# main_schematic.net
KiCad netlist of a schematic drawn in EAGLE
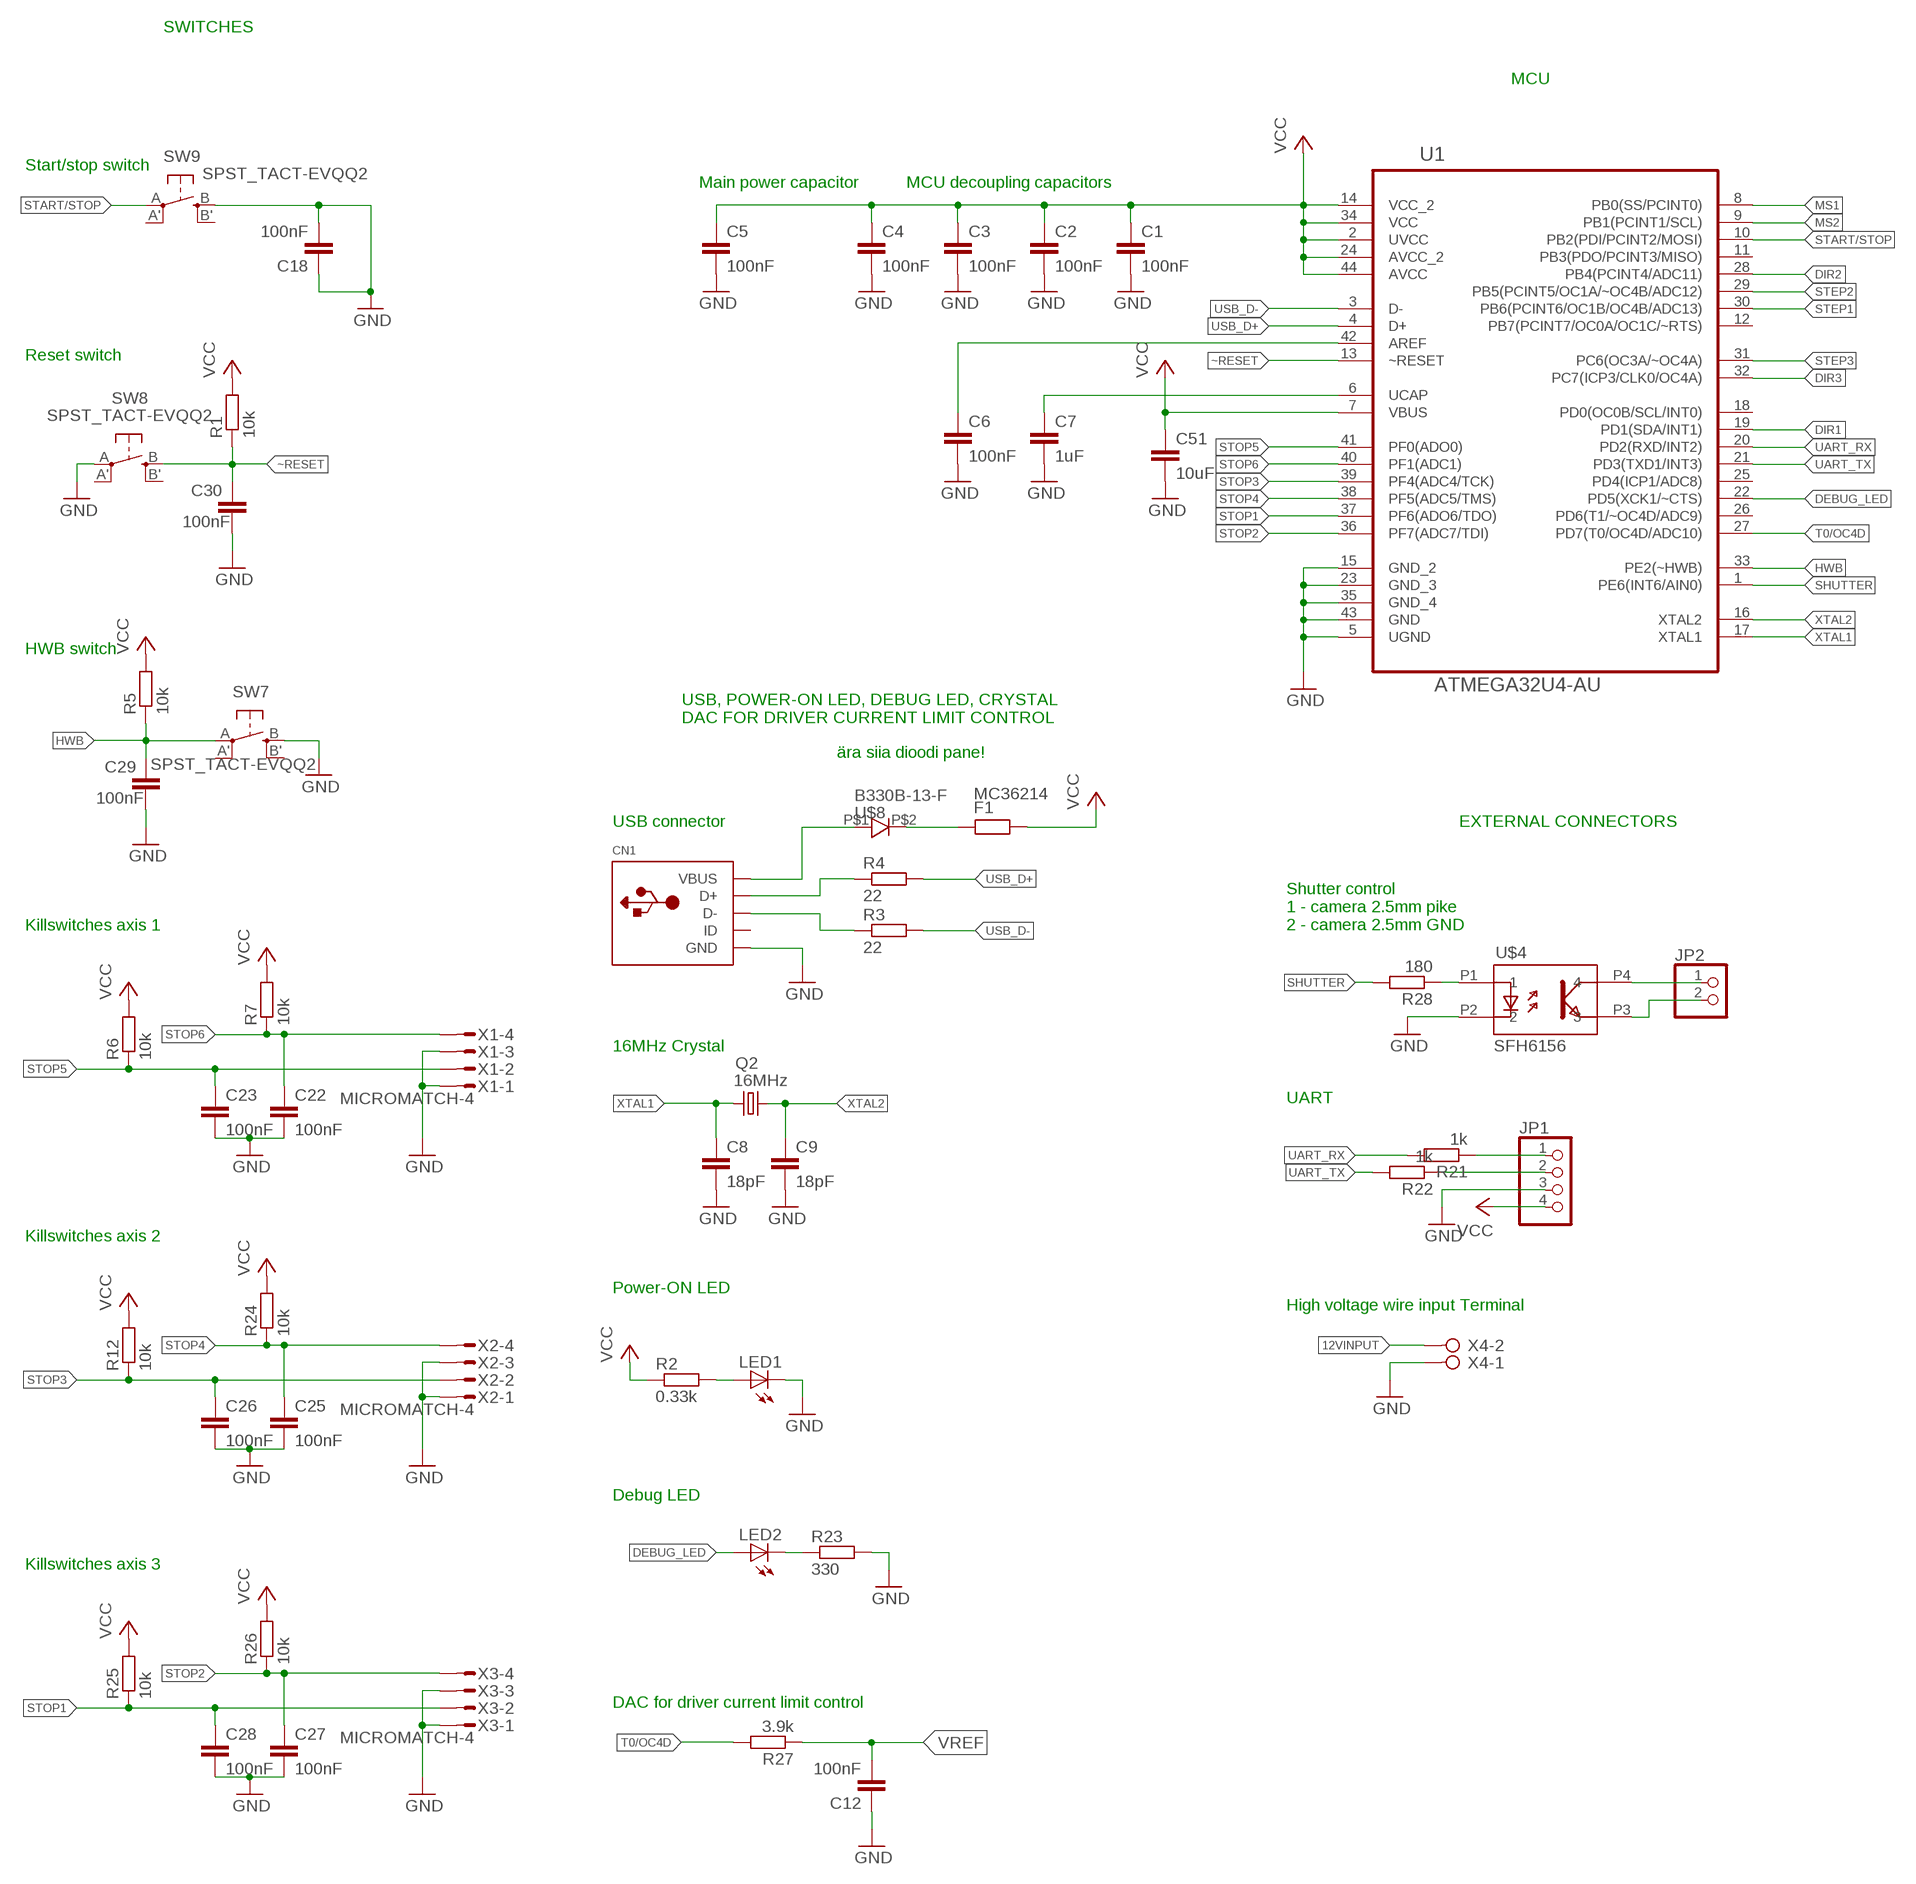
[diagram p0: schematic, sheet 1, part 1 of 2]
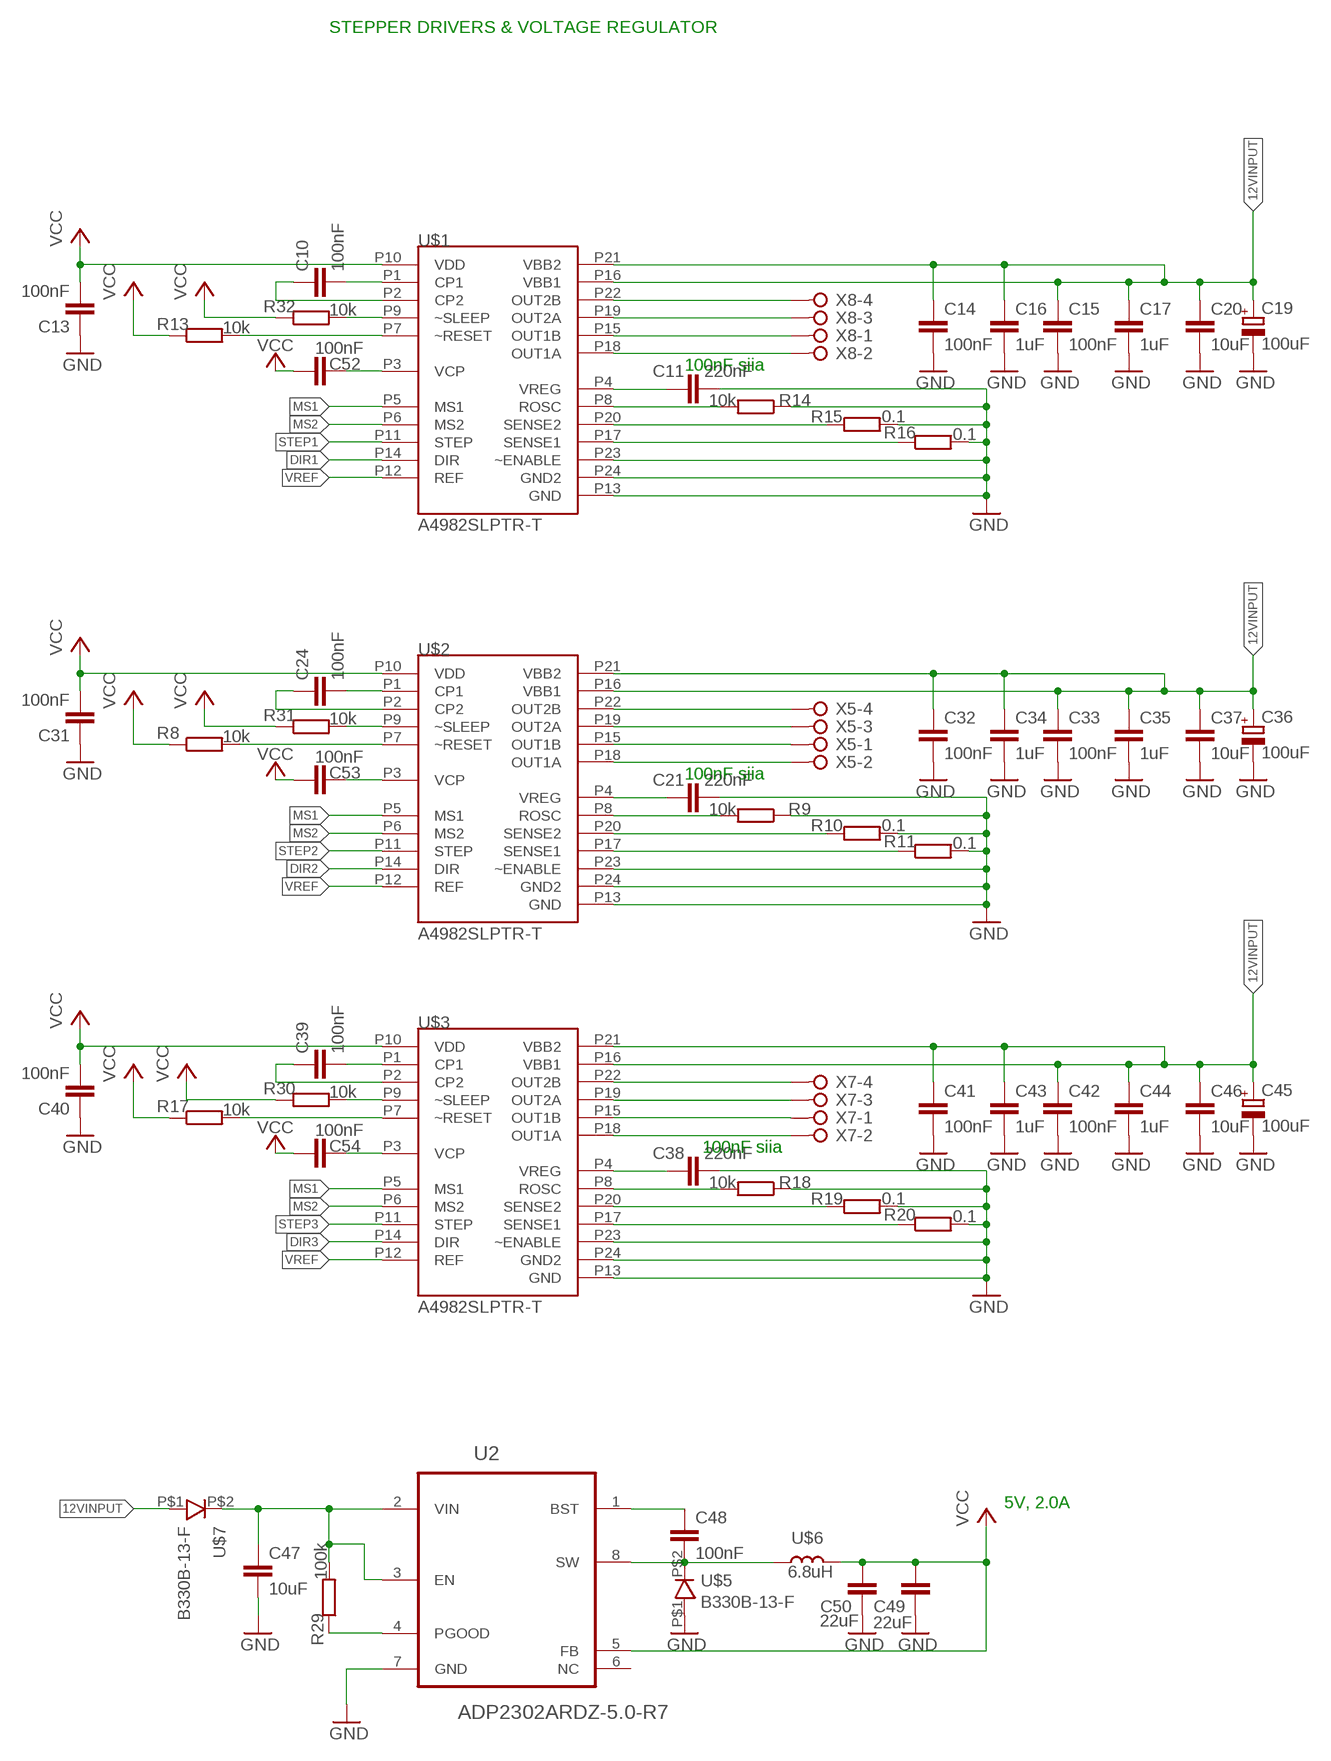
[diagram p1: schematic, sheet 1, part 2 of 2]

(export (version "E")
  (design (tool "Eeschema 10.0.6"))
  (components
    (comp (ref "C1")
      (value "100nF")
      (footprint "eagle-import:C0603K")
      (libsource (lib "eagle-import") (part "C-EUC0603K"))
    )
    (comp (ref "C2")
      (value "100nF")
      (footprint "eagle-import:C0603K")
      (libsource (lib "eagle-import") (part "C-EUC0603K"))
    )
    (comp (ref "C3")
      (value "100nF")
      (footprint "eagle-import:C0603K")
      (libsource (lib "eagle-import") (part "C-EUC0603K"))
    )
    (comp (ref "C4")
      (value "100nF")
      (footprint "eagle-import:C0603K")
      (libsource (lib "eagle-import") (part "C-EUC0603K"))
    )
    (comp (ref "C5")
      (value "100nF")
      (footprint "eagle-import:C0603K")
      (libsource (lib "eagle-import") (part "C-EUC0603K"))
    )
    (comp (ref "C6")
      (value "100nF")
      (footprint "eagle-import:C0603K")
      (libsource (lib "eagle-import") (part "C-EUC0603K"))
    )
    (comp (ref "C7")
      (value "1uF")
      (footprint "eagle-import:C0603K")
      (libsource (lib "eagle-import") (part "C-EUC0603K"))
    )
    (comp (ref "C8")
      (value "18pF")
      (footprint "eagle-import:C0603K")
      (libsource (lib "eagle-import") (part "C-EUC0603K"))
    )
    (comp (ref "C9")
      (value "18pF")
      (footprint "eagle-import:C0603K")
      (libsource (lib "eagle-import") (part "C-EUC0603K"))
    )
    (comp (ref "C10")
      (value "100nF")
      (footprint "eagle-import:C0603K")
      (libsource (lib "eagle-import") (part "C-EUC0603K"))
    )
    (comp (ref "C11")
      (value "220nF")
      (footprint "eagle-import:C0603K")
      (libsource (lib "eagle-import") (part "C-EUC0603K"))
    )
    (comp (ref "C12")
      (value "100nF")
      (footprint "eagle-import:C0603K")
      (libsource (lib "eagle-import") (part "C-EUC0603K"))
    )
    (comp (ref "C13")
      (value "100nF")
      (footprint "eagle-import:C0603K")
      (libsource (lib "eagle-import") (part "C-EUC0603K"))
    )
    (comp (ref "C14")
      (value "100nF")
      (footprint "eagle-import:C0603K")
      (libsource (lib "eagle-import") (part "C-EUC0603K"))
    )
    (comp (ref "C15")
      (value "100nF")
      (footprint "eagle-import:C0603K")
      (libsource (lib "eagle-import") (part "C-EUC0603K"))
    )
    (comp (ref "C16")
      (value "1uF")
      (footprint "eagle-import:C0603K")
      (libsource (lib "eagle-import") (part "C-EUC0603K"))
    )
    (comp (ref "C17")
      (value "1uF")
      (footprint "eagle-import:C0603K")
      (libsource (lib "eagle-import") (part "C-EUC0603K"))
    )
    (comp (ref "C18")
      (value "100nF")
      (footprint "eagle-import:C0603K")
      (libsource (lib "eagle-import") (part "C-EUC0603K"))
    )
    (comp (ref "C19")
      (value "100uF")
      (footprint "eagle-import:E_7260-38R")
      (libsource (lib "eagle-import") (part "CPOL-EUE/7260-38R"))
    )
    (comp (ref "C20")
      (value "10uF")
      (footprint "eagle-import:C1206K")
      (libsource (lib "eagle-import") (part "C-EUC1206K"))
    )
    (comp (ref "C21")
      (value "220nF")
      (footprint "eagle-import:C0603K")
      (libsource (lib "eagle-import") (part "C-EUC0603K"))
    )
    (comp (ref "C22")
      (value "100nF")
      (footprint "eagle-import:C0603K")
      (libsource (lib "eagle-import") (part "C-EUC0603K"))
    )
    (comp (ref "C23")
      (value "100nF")
      (footprint "eagle-import:C0603K")
      (libsource (lib "eagle-import") (part "C-EUC0603K"))
    )
    (comp (ref "C24")
      (value "100nF")
      (footprint "eagle-import:C0603K")
      (libsource (lib "eagle-import") (part "C-EUC0603K"))
    )
    (comp (ref "C25")
      (value "100nF")
      (footprint "eagle-import:C0603K")
      (libsource (lib "eagle-import") (part "C-EUC0603K"))
    )
    (comp (ref "C26")
      (value "100nF")
      (footprint "eagle-import:C0603K")
      (libsource (lib "eagle-import") (part "C-EUC0603K"))
    )
    (comp (ref "C27")
      (value "100nF")
      (footprint "eagle-import:C0603K")
      (libsource (lib "eagle-import") (part "C-EUC0603K"))
    )
    (comp (ref "C28")
      (value "100nF")
      (footprint "eagle-import:C0603K")
      (libsource (lib "eagle-import") (part "C-EUC0603K"))
    )
    (comp (ref "C29")
      (value "100nF")
      (footprint "eagle-import:C0603K")
      (libsource (lib "eagle-import") (part "C-EUC0603K"))
    )
    (comp (ref "C30")
      (value "100nF")
      (footprint "eagle-import:C0603K")
      (libsource (lib "eagle-import") (part "C-EUC0603K"))
    )
    (comp (ref "C31")
      (value "100nF")
      (footprint "eagle-import:C0603K")
      (libsource (lib "eagle-import") (part "C-EUC0603K"))
    )
    (comp (ref "C32")
      (value "100nF")
      (footprint "eagle-import:C0603K")
      (libsource (lib "eagle-import") (part "C-EUC0603K"))
    )
    (comp (ref "C33")
      (value "100nF")
      (footprint "eagle-import:C0603K")
      (libsource (lib "eagle-import") (part "C-EUC0603K"))
    )
    (comp (ref "C34")
      (value "1uF")
      (footprint "eagle-import:C0603K")
      (libsource (lib "eagle-import") (part "C-EUC0603K"))
    )
    (comp (ref "C35")
      (value "1uF")
      (footprint "eagle-import:C0603K")
      (libsource (lib "eagle-import") (part "C-EUC0603K"))
    )
    (comp (ref "C36")
      (value "100uF")
      (footprint "eagle-import:E_7260-38R")
      (libsource (lib "eagle-import") (part "CPOL-EUE/7260-38R"))
    )
    (comp (ref "C37")
      (value "10uF")
      (footprint "eagle-import:C1206K")
      (libsource (lib "eagle-import") (part "C-EUC1206K"))
    )
    (comp (ref "C38")
      (value "220nF")
      (footprint "eagle-import:C0603K")
      (libsource (lib "eagle-import") (part "C-EUC0603K"))
    )
    (comp (ref "C39")
      (value "100nF")
      (footprint "eagle-import:C0603K")
      (libsource (lib "eagle-import") (part "C-EUC0603K"))
    )
    (comp (ref "C40")
      (value "100nF")
      (footprint "eagle-import:C0603K")
      (libsource (lib "eagle-import") (part "C-EUC0603K"))
    )
    (comp (ref "C41")
      (value "100nF")
      (footprint "eagle-import:C0603K")
      (libsource (lib "eagle-import") (part "C-EUC0603K"))
    )
    (comp (ref "C42")
      (value "100nF")
      (footprint "eagle-import:C0603K")
      (libsource (lib "eagle-import") (part "C-EUC0603K"))
    )
    (comp (ref "C43")
      (value "1uF")
      (footprint "eagle-import:C0603K")
      (libsource (lib "eagle-import") (part "C-EUC0603K"))
    )
    (comp (ref "C44")
      (value "1uF")
      (footprint "eagle-import:C0603K")
      (libsource (lib "eagle-import") (part "C-EUC0603K"))
    )
    (comp (ref "C45")
      (value "100uF")
      (footprint "eagle-import:E_7260-38R")
      (libsource (lib "eagle-import") (part "CPOL-EUE/7260-38R"))
    )
    (comp (ref "C46")
      (value "10uF")
      (footprint "eagle-import:C1206K")
      (libsource (lib "eagle-import") (part "C-EUC1206K"))
    )
    (comp (ref "C47")
      (value "10uF")
      (footprint "eagle-import:C1206K")
      (libsource (lib "eagle-import") (part "C-EUC1206K"))
    )
    (comp (ref "C48")
      (value "100nF")
      (footprint "eagle-import:C1206K")
      (libsource (lib "eagle-import") (part "C-EUC1206K"))
    )
    (comp (ref "C49")
      (value "22uF")
      (footprint "eagle-import:C1206K")
      (libsource (lib "eagle-import") (part "C-EUC1206K"))
    )
    (comp (ref "C50")
      (value "22uF")
      (footprint "eagle-import:C1206K")
      (libsource (lib "eagle-import") (part "C-EUC1206K"))
    )
    (comp (ref "C51")
      (value "10uF")
      (footprint "eagle-import:C0805")
      (libsource (lib "eagle-import") (part "C-EUC0805"))
    )
    (comp (ref "C52")
      (value "100nF")
      (footprint "eagle-import:C0603K")
      (libsource (lib "eagle-import") (part "C-EUC0603K"))
    )
    (comp (ref "C53")
      (value "100nF")
      (footprint "eagle-import:C0603K")
      (libsource (lib "eagle-import") (part "C-EUC0603K"))
    )
    (comp (ref "C54")
      (value "100nF")
      (footprint "eagle-import:C0603K")
      (libsource (lib "eagle-import") (part "C-EUC0603K"))
    )
    (comp (ref "CN1")
      (value "USBMINIB")
      (footprint "eagle-import:USB-MINIB")
      (libsource (lib "eagle-import") (part "USBMINIB"))
    )
    (comp (ref "F1")
      (value "MC36214")
      (footprint "eagle-import:MC36214")
      (libsource (lib "eagle-import") (part "MC36214"))
    )
    (comp (ref "JP1")
      (value "PINHD-1X4")
      (footprint "eagle-import:1X04")
      (libsource (lib "eagle-import") (part "PINHD-1X4"))
    )
    (comp (ref "JP2")
      (value "PINHD-1X2")
      (footprint "eagle-import:1X02")
      (libsource (lib "eagle-import") (part "PINHD-1X2"))
    )
    (comp (ref "LED1")
      (value "LEDCHIP-LED0603")
      (footprint "eagle-import:CHIP-LED0603")
      (libsource (lib "eagle-import") (part "LEDCHIP-LED0603"))
    )
    (comp (ref "LED2")
      (value "LEDCHIP-LED0603")
      (footprint "eagle-import:CHIP-LED0603")
      (libsource (lib "eagle-import") (part "LEDCHIP-LED0603"))
    )
    (comp (ref "Q2")
      (value "16MHz")
      (footprint "eagle-import:SM49")
      (libsource (lib "eagle-import") (part "CRYSTALSM49"))
    )
    (comp (ref "R1")
      (value "10k")
      (footprint "eagle-import:R0603")
      (libsource (lib "eagle-import") (part "R-EU_R0603"))
    )
    (comp (ref "R2")
      (value "0.33k")
      (footprint "eagle-import:R0603")
      (libsource (lib "eagle-import") (part "R-EU_R0603"))
    )
    (comp (ref "R3")
      (value "22")
      (footprint "eagle-import:R0603")
      (libsource (lib "eagle-import") (part "R-EU_R0603"))
    )
    (comp (ref "R4")
      (value "22")
      (footprint "eagle-import:R0603")
      (libsource (lib "eagle-import") (part "R-EU_R0603"))
    )
    (comp (ref "R5")
      (value "10k")
      (footprint "eagle-import:R0603")
      (libsource (lib "eagle-import") (part "R-EU_R0603"))
    )
    (comp (ref "R6")
      (value "10k")
      (footprint "eagle-import:R0603")
      (libsource (lib "eagle-import") (part "R-EU_R0603"))
    )
    (comp (ref "R7")
      (value "10k")
      (footprint "eagle-import:R0603")
      (libsource (lib "eagle-import") (part "R-EU_R0603"))
    )
    (comp (ref "R8")
      (value "10k")
      (footprint "eagle-import:R0603")
      (libsource (lib "eagle-import") (part "R-EU_R0603"))
    )
    (comp (ref "R9")
      (value "10k")
      (footprint "eagle-import:R0603")
      (libsource (lib "eagle-import") (part "R-EU_R0603"))
    )
    (comp (ref "R10")
      (value "0.1")
      (footprint "eagle-import:R0805")
      (libsource (lib "eagle-import") (part "R-EU_R0805"))
    )
    (comp (ref "R11")
      (value "0.1")
      (footprint "eagle-import:R0805")
      (libsource (lib "eagle-import") (part "R-EU_R0805"))
    )
    (comp (ref "R12")
      (value "10k")
      (footprint "eagle-import:R0603")
      (libsource (lib "eagle-import") (part "R-EU_R0603"))
    )
    (comp (ref "R13")
      (value "10k")
      (footprint "eagle-import:R0603")
      (libsource (lib "eagle-import") (part "R-EU_R0603"))
    )
    (comp (ref "R14")
      (value "10k")
      (footprint "eagle-import:R0603")
      (libsource (lib "eagle-import") (part "R-EU_R0603"))
    )
    (comp (ref "R15")
      (value "0.1")
      (footprint "eagle-import:R0805")
      (libsource (lib "eagle-import") (part "R-EU_R0805"))
    )
    (comp (ref "R16")
      (value "0.1")
      (footprint "eagle-import:R0805")
      (libsource (lib "eagle-import") (part "R-EU_R0805"))
    )
    (comp (ref "R17")
      (value "10k")
      (footprint "eagle-import:R0603")
      (libsource (lib "eagle-import") (part "R-EU_R0603"))
    )
    (comp (ref "R18")
      (value "10k")
      (footprint "eagle-import:R0603")
      (libsource (lib "eagle-import") (part "R-EU_R0603"))
    )
    (comp (ref "R19")
      (value "0.1")
      (footprint "eagle-import:R0805")
      (libsource (lib "eagle-import") (part "R-EU_R0805"))
    )
    (comp (ref "R20")
      (value "0.1")
      (footprint "eagle-import:R0805")
      (libsource (lib "eagle-import") (part "R-EU_R0805"))
    )
    (comp (ref "R21")
      (value "1k")
      (footprint "eagle-import:R0603")
      (libsource (lib "eagle-import") (part "R-EU_R0603"))
    )
    (comp (ref "R22")
      (value "1k")
      (footprint "eagle-import:R0603")
      (libsource (lib "eagle-import") (part "R-EU_R0603"))
    )
    (comp (ref "R23")
      (value "330")
      (footprint "eagle-import:R0603")
      (libsource (lib "eagle-import") (part "R-EU_R0603"))
    )
    (comp (ref "R24")
      (value "10k")
      (footprint "eagle-import:R0603")
      (libsource (lib "eagle-import") (part "R-EU_R0603"))
    )
    (comp (ref "R25")
      (value "10k")
      (footprint "eagle-import:R0603")
      (libsource (lib "eagle-import") (part "R-EU_R0603"))
    )
    (comp (ref "R26")
      (value "10k")
      (footprint "eagle-import:R0603")
      (libsource (lib "eagle-import") (part "R-EU_R0603"))
    )
    (comp (ref "R27")
      (value "3.9k")
      (footprint "eagle-import:R0603")
      (libsource (lib "eagle-import") (part "R-EU_R0603"))
    )
    (comp (ref "R28")
      (value "180")
      (footprint "eagle-import:R0603")
      (libsource (lib "eagle-import") (part "R-EU_R0603"))
    )
    (comp (ref "R29")
      (value "100k")
      (footprint "eagle-import:R0603")
      (libsource (lib "eagle-import") (part "R-EU_R0603"))
    )
    (comp (ref "R30")
      (value "10k")
      (footprint "eagle-import:R0603")
      (libsource (lib "eagle-import") (part "R-EU_R0603"))
    )
    (comp (ref "R31")
      (value "10k")
      (footprint "eagle-import:R0603")
      (libsource (lib "eagle-import") (part "R-EU_R0603"))
    )
    (comp (ref "R32")
      (value "10k")
      (footprint "eagle-import:R0603")
      (libsource (lib "eagle-import") (part "R-EU_R0603"))
    )
    (comp (ref "SW7")
      (value "SPST_TACT-EVQQ2")
      (footprint "eagle-import:EVQ-Q2")
      (libsource (lib "eagle-import") (part "SPST_TACT-EVQQ2"))
    )
    (comp (ref "SW8")
      (value "SPST_TACT-EVQQ2")
      (footprint "eagle-import:EVQ-Q2")
      (libsource (lib "eagle-import") (part "SPST_TACT-EVQQ2"))
    )
    (comp (ref "SW9")
      (value "SPST_TACT-EVQQ2")
      (footprint "eagle-import:EVQ-Q2")
      (libsource (lib "eagle-import") (part "SPST_TACT-EVQQ2"))
    )
    (comp (ref "U$1")
      (value "A4982SLPTR-T")
      (footprint "eagle-import:TSSOP_24")
      (libsource (lib "eagle-import") (part "A4982SLPTR-T"))
    )
    (comp (ref "U$2")
      (value "A4982SLPTR-T")
      (footprint "eagle-import:TSSOP_24")
      (libsource (lib "eagle-import") (part "A4982SLPTR-T"))
    )
    (comp (ref "U$3")
      (value "A4982SLPTR-T")
      (footprint "eagle-import:TSSOP_24")
      (libsource (lib "eagle-import") (part "A4982SLPTR-T"))
    )
    (comp (ref "U$4")
      (value "SFH6156")
      (footprint "eagle-import:SFH6165")
      (libsource (lib "eagle-import") (part "SFH6156"))
    )
    (comp (ref "U$5")
      (value "B330B-13-F")
      (footprint "eagle-import:B330B-13-F")
      (libsource (lib "eagle-import") (part "SCHOTTK_YB330B-13-F"))
    )
    (comp (ref "U$6")
      (value "6.8uH")
      (footprint "eagle-import:VLF10040")
      (libsource (lib "eagle-import") (part "VLF10040"))
    )
    (comp (ref "U$7")
      (value "B330B-13-F")
      (footprint "eagle-import:B330B-13-F")
      (libsource (lib "eagle-import") (part "SCHOTTK_YB330B-13-F"))
    )
    (comp (ref "U$8")
      (value "B330B-13-F")
      (footprint "eagle-import:B330B-13-F")
      (libsource (lib "eagle-import") (part "SCHOTTK_YB330B-13-F"))
    )
    (comp (ref "U1")
      (value "ATMEGA32U4-AU")
      (footprint "eagle-import:QFP80P1200X1200X120-44N")
      (libsource (lib "eagle-import") (part "ATMEGA32U4-AU"))
    )
    (comp (ref "U2")
      (value "ADP2302ARDZ-5.0-R7")
      (footprint "eagle-import:SOIC127P600X175-9N")
      (libsource (lib "eagle-import") (part "ADP2302ARDZ-5.0-R7"))
    )
    (comp (ref "X1")
      (value "MICROMATCH-4")
      (footprint "eagle-import:MICROMATCH-4")
      (fields (field (name "MPN") "7-215464-4"))
      (libsource (lib "eagle-import") (part "MICROMATCH-4"))
    )
    (comp (ref "X2")
      (value "MICROMATCH-4")
      (footprint "eagle-import:MICROMATCH-4")
      (fields (field (name "MPN") "7-215464-4"))
      (libsource (lib "eagle-import") (part "MICROMATCH-4"))
    )
    (comp (ref "X3")
      (value "MICROMATCH-4")
      (footprint "eagle-import:MICROMATCH-4")
      (fields (field (name "MPN") "7-215464-4"))
      (libsource (lib "eagle-import") (part "MICROMATCH-4"))
    )
    (comp (ref "X4")
      (value "W237-02P")
      (footprint "eagle-import:W237-132")
      (libsource (lib "eagle-import") (part "W237-02P"))
    )
    (comp (ref "X5")
      (value "W237-04P")
      (footprint "eagle-import:W237-4P")
      (libsource (lib "eagle-import") (part "W237-04P"))
    )
    (comp (ref "X7")
      (value "W237-04P")
      (footprint "eagle-import:W237-4P")
      (libsource (lib "eagle-import") (part "W237-04P"))
    )
    (comp (ref "X8")
      (value "W237-04P")
      (footprint "eagle-import:W237-4P")
      (libsource (lib "eagle-import") (part "W237-04P"))
    )
  )
  (nets
    (net (code "1") (name "/~{RESET}") (class "Default")
      (node (ref "C30") (pin "1") (pinfunction "1_1") (pintype "passive"))
      (node (ref "R1") (pin "1") (pinfunction "1_1") (pintype "passive"))
      (node (ref "SW8") (pin "B") (pinfunction "S_B") (pintype "passive"))
      (node (ref "U1") (pin "13") (pinfunction "~{RESET}_13") (pintype "input"))
    )
    (net (code "2") (name "12VINPUT") (class "Default")
      (node (ref "C14") (pin "1") (pinfunction "1_1") (pintype "passive"))
      (node (ref "C15") (pin "1") (pinfunction "1_1") (pintype "passive"))
      (node (ref "C16") (pin "1") (pinfunction "1_1") (pintype "passive"))
      (node (ref "C17") (pin "1") (pinfunction "1_1") (pintype "passive"))
      (node (ref "C19") (pin "+") (pinfunction "+_+") (pintype "passive"))
      (node (ref "C20") (pin "1") (pinfunction "1_1") (pintype "passive"))
      (node (ref "C32") (pin "1") (pinfunction "1_1") (pintype "passive"))
      (node (ref "C33") (pin "1") (pinfunction "1_1") (pintype "passive"))
      (node (ref "C34") (pin "1") (pinfunction "1_1") (pintype "passive"))
      (node (ref "C35") (pin "1") (pinfunction "1_1") (pintype "passive"))
      (node (ref "C36") (pin "+") (pinfunction "+_+") (pintype "passive"))
      (node (ref "C37") (pin "1") (pinfunction "1_1") (pintype "passive"))
      (node (ref "C41") (pin "1") (pinfunction "1_1") (pintype "passive"))
      (node (ref "C42") (pin "1") (pinfunction "1_1") (pintype "passive"))
      (node (ref "C43") (pin "1") (pinfunction "1_1") (pintype "passive"))
      (node (ref "C44") (pin "1") (pinfunction "1_1") (pintype "passive"))
      (node (ref "C45") (pin "+") (pinfunction "+_+") (pintype "passive"))
      (node (ref "C46") (pin "1") (pinfunction "1_1") (pintype "passive"))
      (node (ref "U$1") (pin "P16") (pinfunction "VBB1_P16") (pintype "bidirectional"))
      (node (ref "U$1") (pin "P21") (pinfunction "VBB2_P21") (pintype "bidirectional"))
      (node (ref "U$2") (pin "P16") (pinfunction "VBB1_P16") (pintype "bidirectional"))
      (node (ref "U$2") (pin "P21") (pinfunction "VBB2_P21") (pintype "bidirectional"))
      (node (ref "U$3") (pin "P16") (pinfunction "VBB1_P16") (pintype "bidirectional"))
      (node (ref "U$3") (pin "P21") (pinfunction "VBB2_P21") (pintype "bidirectional"))
      (node (ref "U$7") (pin "P$1") (pinfunction "P$1_P$1") (pintype "bidirectional"))
      (node (ref "X4") (pin "2") (pinfunction "KL_2") (pintype "passive"))
    )
    (net (code "3") (name "DEBUG_LED") (class "Default")
      (node (ref "LED2") (pin "A") (pinfunction "A_A") (pintype "passive"))
      (node (ref "U1") (pin "22") (pinfunction "PD5(XCK1/~{CTS})_22") (pintype "bidirectional"))
    )
    (net (code "4") (name "DIR1") (class "Default")
      (node (ref "U$1") (pin "P14") (pinfunction "DIR_P14") (pintype "bidirectional"))
      (node (ref "U1") (pin "19") (pinfunction "PD1(SDA/INT1)_19") (pintype "bidirectional"))
    )
    (net (code "5") (name "DIR2") (class "Default")
      (node (ref "U$2") (pin "P14") (pinfunction "DIR_P14") (pintype "bidirectional"))
      (node (ref "U1") (pin "28") (pinfunction "PB4(PCINT4/ADC11)_28") (pintype "bidirectional"))
    )
    (net (code "6") (name "DIR3") (class "Default")
      (node (ref "U$3") (pin "P14") (pinfunction "DIR_P14") (pintype "bidirectional"))
      (node (ref "U1") (pin "32") (pinfunction "PC7(ICP3/CLK0/OC4A)_32") (pintype "bidirectional"))
    )
    (net (code "7") (name "GND") (class "Default")
      (node (ref "C1") (pin "2") (pinfunction "2_2") (pintype "passive"))
      (node (ref "C11") (pin "1") (pinfunction "1_1") (pintype "passive"))
      (node (ref "C12") (pin "1") (pinfunction "1_1") (pintype "passive"))
      (node (ref "C13") (pin "1") (pinfunction "1_1") (pintype "passive"))
      (node (ref "C14") (pin "2") (pinfunction "2_2") (pintype "passive"))
      (node (ref "C15") (pin "2") (pinfunction "2_2") (pintype "passive"))
      (node (ref "C16") (pin "2") (pinfunction "2_2") (pintype "passive"))
      (node (ref "C17") (pin "2") (pinfunction "2_2") (pintype "passive"))
      (node (ref "C18") (pin "1") (pinfunction "1_1") (pintype "passive"))
      (node (ref "C18") (pin "2") (pinfunction "2_2") (pintype "passive"))
      (node (ref "C19") (pin "-") (pinfunction "-_-") (pintype "passive"))
      (node (ref "C2") (pin "2") (pinfunction "2_2") (pintype "passive"))
      (node (ref "C20") (pin "2") (pinfunction "2_2") (pintype "passive"))
      (node (ref "C21") (pin "1") (pinfunction "1_1") (pintype "passive"))
      (node (ref "C22") (pin "2") (pinfunction "2_2") (pintype "passive"))
      (node (ref "C23") (pin "2") (pinfunction "2_2") (pintype "passive"))
      (node (ref "C25") (pin "2") (pinfunction "2_2") (pintype "passive"))
      (node (ref "C26") (pin "2") (pinfunction "2_2") (pintype "passive"))
      (node (ref "C27") (pin "2") (pinfunction "2_2") (pintype "passive"))
      (node (ref "C28") (pin "2") (pinfunction "2_2") (pintype "passive"))
      (node (ref "C29") (pin "2") (pinfunction "2_2") (pintype "passive"))
      (node (ref "C3") (pin "2") (pinfunction "2_2") (pintype "passive"))
      (node (ref "C30") (pin "2") (pinfunction "2_2") (pintype "passive"))
      (node (ref "C31") (pin "1") (pinfunction "1_1") (pintype "passive"))
      (node (ref "C32") (pin "2") (pinfunction "2_2") (pintype "passive"))
      (node (ref "C33") (pin "2") (pinfunction "2_2") (pintype "passive"))
      (node (ref "C34") (pin "2") (pinfunction "2_2") (pintype "passive"))
      (node (ref "C35") (pin "2") (pinfunction "2_2") (pintype "passive"))
      (node (ref "C36") (pin "-") (pinfunction "-_-") (pintype "passive"))
      (node (ref "C37") (pin "2") (pinfunction "2_2") (pintype "passive"))
      (node (ref "C38") (pin "1") (pinfunction "1_1") (pintype "passive"))
      (node (ref "C4") (pin "2") (pinfunction "2_2") (pintype "passive"))
      (node (ref "C40") (pin "1") (pinfunction "1_1") (pintype "passive"))
      (node (ref "C41") (pin "2") (pinfunction "2_2") (pintype "passive"))
      (node (ref "C42") (pin "2") (pinfunction "2_2") (pintype "passive"))
      (node (ref "C43") (pin "2") (pinfunction "2_2") (pintype "passive"))
      (node (ref "C44") (pin "2") (pinfunction "2_2") (pintype "passive"))
      (node (ref "C45") (pin "-") (pinfunction "-_-") (pintype "passive"))
      (node (ref "C46") (pin "2") (pinfunction "2_2") (pintype "passive"))
      (node (ref "C47") (pin "2") (pinfunction "2_2") (pintype "passive"))
      (node (ref "C49") (pin "1") (pinfunction "1_1") (pintype "passive"))
      (node (ref "C5") (pin "2") (pinfunction "2_2") (pintype "passive"))
      (node (ref "C50") (pin "1") (pinfunction "1_1") (pintype "passive"))
      (node (ref "C51") (pin "2") (pinfunction "2_2") (pintype "passive"))
      (node (ref "C6") (pin "2") (pinfunction "2_2") (pintype "passive"))
      (node (ref "C7") (pin "2") (pinfunction "2_2") (pintype "passive"))
      (node (ref "C8") (pin "2") (pinfunction "2_2") (pintype "passive"))
      (node (ref "C9") (pin "2") (pinfunction "2_2") (pintype "passive"))
      (node (ref "CN1") (pin "GND") (pinfunction "GND_GND") (pintype "power_in"))
      (node (ref "JP1") (pin "3") (pinfunction "3_3") (pintype "passive"))
      (node (ref "LED1") (pin "C") (pinfunction "C_C") (pintype "passive"))
      (node (ref "R10") (pin "2") (pinfunction "2_2") (pintype "passive"))
      (node (ref "R11") (pin "2") (pinfunction "2_2") (pintype "passive"))
      (node (ref "R14") (pin "1") (pinfunction "1_1") (pintype "passive"))
      (node (ref "R15") (pin "2") (pinfunction "2_2") (pintype "passive"))
      (node (ref "R16") (pin "2") (pinfunction "2_2") (pintype "passive"))
      (node (ref "R18") (pin "1") (pinfunction "1_1") (pintype "passive"))
      (node (ref "R19") (pin "2") (pinfunction "2_2") (pintype "passive"))
      (node (ref "R20") (pin "2") (pinfunction "2_2") (pintype "passive"))
      (node (ref "R23") (pin "2") (pinfunction "2_2") (pintype "passive"))
      (node (ref "R9") (pin "1") (pinfunction "1_1") (pintype "passive"))
      (node (ref "SW7") (pin "B") (pinfunction "S_B") (pintype "passive"))
      (node (ref "SW8") (pin "A") (pinfunction "P_A") (pintype "passive"))
      (node (ref "SW9") (pin "B") (pinfunction "S_B") (pintype "passive"))
      (node (ref "U$1") (pin "P13") (pinfunction "GND_P13") (pintype "bidirectional"))
      (node (ref "U$1") (pin "P23") (pinfunction "~{ENABLE}_P23") (pintype "bidirectional"))
      (node (ref "U$1") (pin "P24") (pinfunction "GND2_P24") (pintype "bidirectional"))
      (node (ref "U$2") (pin "P13") (pinfunction "GND_P13") (pintype "bidirectional"))
      (node (ref "U$2") (pin "P23") (pinfunction "~{ENABLE}_P23") (pintype "bidirectional"))
      (node (ref "U$2") (pin "P24") (pinfunction "GND2_P24") (pintype "bidirectional"))
      (node (ref "U$3") (pin "P13") (pinfunction "GND_P13") (pintype "bidirectional"))
      (node (ref "U$3") (pin "P23") (pinfunction "~{ENABLE}_P23") (pintype "bidirectional"))
      (node (ref "U$3") (pin "P24") (pinfunction "GND2_P24") (pintype "bidirectional"))
      (node (ref "U$4") (pin "P2") (pinfunction "2_P2") (pintype "bidirectional"))
      (node (ref "U$5") (pin "P$1") (pinfunction "P$1_P$1") (pintype "bidirectional"))
      (node (ref "U1") (pin "15") (pinfunction "GND_2_15") (pintype "passive"))
      (node (ref "U1") (pin "23") (pinfunction "GND_3_23") (pintype "passive"))
      (node (ref "U1") (pin "35") (pinfunction "GND_4_35") (pintype "passive"))
      (node (ref "U1") (pin "43") (pinfunction "GND_43") (pintype "passive"))
      (node (ref "U1") (pin "5") (pinfunction "UGND_5") (pintype "passive"))
      (node (ref "U2") (pin "7") (pinfunction "GND_7") (pintype "passive"))
      (node (ref "X1") (pin "1") (pinfunction "S_1") (pintype "passive"))
      (node (ref "X1") (pin "3") (pinfunction "S_3") (pintype "passive"))
      (node (ref "X2") (pin "1") (pinfunction "S_1") (pintype "passive"))
      (node (ref "X2") (pin "3") (pinfunction "S_3") (pintype "passive"))
      (node (ref "X3") (pin "1") (pinfunction "S_1") (pintype "passive"))
      (node (ref "X3") (pin "3") (pinfunction "S_3") (pintype "passive"))
      (node (ref "X4") (pin "1") (pinfunction "KL_1") (pintype "passive"))
    )
    (net (code "8") (name "HWB") (class "Default")
      (node (ref "C29") (pin "1") (pinfunction "1_1") (pintype "passive"))
      (node (ref "R5") (pin "1") (pinfunction "1_1") (pintype "passive"))
      (node (ref "SW7") (pin "A") (pinfunction "P_A") (pintype "passive"))
      (node (ref "U1") (pin "33") (pinfunction "PE2(~{HWB})_33") (pintype "bidirectional"))
    )
    (net (code "9") (name "MS1") (class "Default")
      (node (ref "U$1") (pin "P5") (pinfunction "MS1_P5") (pintype "bidirectional"))
      (node (ref "U$2") (pin "P5") (pinfunction "MS1_P5") (pintype "bidirectional"))
      (node (ref "U$3") (pin "P5") (pinfunction "MS1_P5") (pintype "bidirectional"))
      (node (ref "U1") (pin "8") (pinfunction "PB0(SS/PCINT0)_8") (pintype "bidirectional"))
    )
    (net (code "10") (name "MS2") (class "Default")
      (node (ref "U$1") (pin "P6") (pinfunction "MS2_P6") (pintype "bidirectional"))
      (node (ref "U$2") (pin "P6") (pinfunction "MS2_P6") (pintype "bidirectional"))
      (node (ref "U$3") (pin "P6") (pinfunction "MS2_P6") (pintype "bidirectional"))
      (node (ref "U1") (pin "9") (pinfunction "PB1(PCINT1/SCL)_9") (pintype "bidirectional"))
    )
    (net (code "11") (name "Net-(CN1-PadD+)") (class "Default")
      (node (ref "CN1") (pin "D+") (pinfunction "D+_D+") (pintype "bidirectional"))
      (node (ref "R4") (pin "1") (pinfunction "1_1") (pintype "passive"))
    )
    (net (code "12") (name "Net-(CN1-PadD-)") (class "Default")
      (node (ref "CN1") (pin "D-") (pinfunction "D-_D-") (pintype "bidirectional"))
      (node (ref "R3") (pin "1") (pinfunction "1_1") (pintype "passive"))
    )
    (net (code "13") (name "Net-(CN1-PadVBUS)") (class "Default")
      (node (ref "CN1") (pin "VBUS") (pinfunction "VBUS_VBUS") (pintype "power_in"))
      (node (ref "U$8") (pin "P$1") (pinfunction "P$1_P$1") (pintype "bidirectional"))
    )
    (net (code "14") (name "Net-(F1-PadP$1)") (class "Default")
      (node (ref "F1") (pin "P$1") (pinfunction "P$1_P$1") (pintype "bidirectional"))
      (node (ref "U$8") (pin "P$2") (pinfunction "P$2_P$2") (pintype "bidirectional"))
    )
    (net (code "15") (name "Net-(JP1-Pad1)") (class "Default")
      (node (ref "JP1") (pin "1") (pinfunction "1_1") (pintype "passive"))
      (node (ref "R21") (pin "1") (pinfunction "1_1") (pintype "passive"))
    )
    (net (code "16") (name "Net-(JP1-Pad2)") (class "Default")
      (node (ref "JP1") (pin "2") (pinfunction "2_2") (pintype "passive"))
      (node (ref "R22") (pin "1") (pinfunction "1_1") (pintype "passive"))
    )
    (net (code "17") (name "Net-(LED1-PadA)") (class "Default")
      (node (ref "LED1") (pin "A") (pinfunction "A_A") (pintype "passive"))
      (node (ref "R2") (pin "2") (pinfunction "2_2") (pintype "passive"))
    )
    (net (code "18") (name "Net-(LED2-PadC)") (class "Default")
      (node (ref "LED2") (pin "C") (pinfunction "C_C") (pintype "passive"))
      (node (ref "R23") (pin "1") (pinfunction "1_1") (pintype "passive"))
    )
    (net (code "19") (name "Net-(U$1-CP1)") (class "Default")
      (node (ref "C10") (pin "2") (pinfunction "2_2") (pintype "passive"))
      (node (ref "U$1") (pin "P1") (pinfunction "CP1_P1") (pintype "bidirectional"))
    )
    (net (code "20") (name "Net-(U$1-CP2)") (class "Default")
      (node (ref "C10") (pin "1") (pinfunction "1_1") (pintype "passive"))
      (node (ref "U$1") (pin "P2") (pinfunction "CP2_P2") (pintype "bidirectional"))
    )
    (net (code "21") (name "Net-(U$1-OUT1A)") (class "Default")
      (node (ref "U$1") (pin "P18") (pinfunction "OUT1A_P18") (pintype "bidirectional"))
      (node (ref "X8") (pin "2") (pinfunction "KL_2") (pintype "passive"))
    )
    (net (code "22") (name "Net-(U$1-OUT1B)") (class "Default")
      (node (ref "U$1") (pin "P15") (pinfunction "OUT1B_P15") (pintype "bidirectional"))
      (node (ref "X8") (pin "1") (pinfunction "KL_1") (pintype "passive"))
    )
    (net (code "23") (name "Net-(U$1-OUT2A)") (class "Default")
      (node (ref "U$1") (pin "P19") (pinfunction "OUT2A_P19") (pintype "bidirectional"))
      (node (ref "X8") (pin "3") (pinfunction "KL_3") (pintype "passive"))
    )
    (net (code "24") (name "Net-(U$1-OUT2B)") (class "Default")
      (node (ref "U$1") (pin "P22") (pinfunction "OUT2B_P22") (pintype "bidirectional"))
      (node (ref "X8") (pin "4") (pinfunction "KL_4") (pintype "passive"))
    )
    (net (code "25") (name "Net-(U$1-ROSC)") (class "Default")
      (node (ref "R14") (pin "2") (pinfunction "2_2") (pintype "passive"))
      (node (ref "U$1") (pin "P8") (pinfunction "ROSC_P8") (pintype "bidirectional"))
    )
    (net (code "26") (name "Net-(U$1-SENSE1)") (class "Default")
      (node (ref "R16") (pin "1") (pinfunction "1_1") (pintype "passive"))
      (node (ref "U$1") (pin "P17") (pinfunction "SENSE1_P17") (pintype "bidirectional"))
    )
    (net (code "27") (name "Net-(U$1-SENSE2)") (class "Default")
      (node (ref "R15") (pin "1") (pinfunction "1_1") (pintype "passive"))
      (node (ref "U$1") (pin "P20") (pinfunction "SENSE2_P20") (pintype "bidirectional"))
    )
    (net (code "28") (name "Net-(U$1-VCP)") (class "Default")
      (node (ref "C52") (pin "1") (pinfunction "1_1") (pintype "passive"))
      (node (ref "U$1") (pin "P3") (pinfunction "VCP_P3") (pintype "bidirectional"))
    )
    (net (code "29") (name "Net-(U$1-VREG)") (class "Default")
      (node (ref "C11") (pin "2") (pinfunction "2_2") (pintype "passive"))
      (node (ref "U$1") (pin "P4") (pinfunction "VREG_P4") (pintype "bidirectional"))
    )
    (net (code "30") (name "Net-(U$1-~{RESET})") (class "Default")
      (node (ref "R13") (pin "2") (pinfunction "2_2") (pintype "passive"))
      (node (ref "U$1") (pin "P7") (pinfunction "~{RESET}_P7") (pintype "bidirectional"))
    )
    (net (code "31") (name "Net-(U$1-~{SLEEP})") (class "Default")
      (node (ref "R32") (pin "2") (pinfunction "2_2") (pintype "passive"))
      (node (ref "U$1") (pin "P9") (pinfunction "~{SLEEP}_P9") (pintype "bidirectional"))
    )
    (net (code "32") (name "Net-(U$2-CP1)") (class "Default")
      (node (ref "C24") (pin "2") (pinfunction "2_2") (pintype "passive"))
      (node (ref "U$2") (pin "P1") (pinfunction "CP1_P1") (pintype "bidirectional"))
    )
    (net (code "33") (name "Net-(U$2-CP2)") (class "Default")
      (node (ref "C24") (pin "1") (pinfunction "1_1") (pintype "passive"))
      (node (ref "U$2") (pin "P2") (pinfunction "CP2_P2") (pintype "bidirectional"))
    )
    (net (code "34") (name "Net-(U$2-OUT1A)") (class "Default")
      (node (ref "U$2") (pin "P18") (pinfunction "OUT1A_P18") (pintype "bidirectional"))
      (node (ref "X5") (pin "2") (pinfunction "KL_2") (pintype "passive"))
    )
    (net (code "35") (name "Net-(U$2-OUT1B)") (class "Default")
      (node (ref "U$2") (pin "P15") (pinfunction "OUT1B_P15") (pintype "bidirectional"))
      (node (ref "X5") (pin "1") (pinfunction "KL_1") (pintype "passive"))
    )
    (net (code "36") (name "Net-(U$2-OUT2A)") (class "Default")
      (node (ref "U$2") (pin "P19") (pinfunction "OUT2A_P19") (pintype "bidirectional"))
      (node (ref "X5") (pin "3") (pinfunction "KL_3") (pintype "passive"))
    )
    (net (code "37") (name "Net-(U$2-OUT2B)") (class "Default")
      (node (ref "U$2") (pin "P22") (pinfunction "OUT2B_P22") (pintype "bidirectional"))
      (node (ref "X5") (pin "4") (pinfunction "KL_4") (pintype "passive"))
    )
    (net (code "38") (name "Net-(U$2-ROSC)") (class "Default")
      (node (ref "R9") (pin "2") (pinfunction "2_2") (pintype "passive"))
      (node (ref "U$2") (pin "P8") (pinfunction "ROSC_P8") (pintype "bidirectional"))
    )
    (net (code "39") (name "Net-(U$2-SENSE1)") (class "Default")
      (node (ref "R11") (pin "1") (pinfunction "1_1") (pintype "passive"))
      (node (ref "U$2") (pin "P17") (pinfunction "SENSE1_P17") (pintype "bidirectional"))
    )
    (net (code "40") (name "Net-(U$2-SENSE2)") (class "Default")
      (node (ref "R10") (pin "1") (pinfunction "1_1") (pintype "passive"))
      (node (ref "U$2") (pin "P20") (pinfunction "SENSE2_P20") (pintype "bidirectional"))
    )
    (net (code "41") (name "Net-(U$2-VCP)") (class "Default")
      (node (ref "C53") (pin "1") (pinfunction "1_1") (pintype "passive"))
      (node (ref "U$2") (pin "P3") (pinfunction "VCP_P3") (pintype "bidirectional"))
    )
    (net (code "42") (name "Net-(U$2-VREG)") (class "Default")
      (node (ref "C21") (pin "2") (pinfunction "2_2") (pintype "passive"))
      (node (ref "U$2") (pin "P4") (pinfunction "VREG_P4") (pintype "bidirectional"))
    )
    (net (code "43") (name "Net-(U$2-~{RESET})") (class "Default")
      (node (ref "R8") (pin "2") (pinfunction "2_2") (pintype "passive"))
      (node (ref "U$2") (pin "P7") (pinfunction "~{RESET}_P7") (pintype "bidirectional"))
    )
    (net (code "44") (name "Net-(U$2-~{SLEEP})") (class "Default")
      (node (ref "R31") (pin "2") (pinfunction "2_2") (pintype "passive"))
      (node (ref "U$2") (pin "P9") (pinfunction "~{SLEEP}_P9") (pintype "bidirectional"))
    )
    (net (code "45") (name "Net-(U$3-CP1)") (class "Default")
      (node (ref "C39") (pin "2") (pinfunction "2_2") (pintype "passive"))
      (node (ref "U$3") (pin "P1") (pinfunction "CP1_P1") (pintype "bidirectional"))
    )
    (net (code "46") (name "Net-(U$3-CP2)") (class "Default")
      (node (ref "C39") (pin "1") (pinfunction "1_1") (pintype "passive"))
      (node (ref "U$3") (pin "P2") (pinfunction "CP2_P2") (pintype "bidirectional"))
    )
    (net (code "47") (name "Net-(U$3-OUT1A)") (class "Default")
      (node (ref "U$3") (pin "P18") (pinfunction "OUT1A_P18") (pintype "bidirectional"))
      (node (ref "X7") (pin "2") (pinfunction "KL_2") (pintype "passive"))
    )
    (net (code "48") (name "Net-(U$3-OUT1B)") (class "Default")
      (node (ref "U$3") (pin "P15") (pinfunction "OUT1B_P15") (pintype "bidirectional"))
      (node (ref "X7") (pin "1") (pinfunction "KL_1") (pintype "passive"))
    )
    (net (code "49") (name "Net-(U$3-OUT2A)") (class "Default")
      (node (ref "U$3") (pin "P19") (pinfunction "OUT2A_P19") (pintype "bidirectional"))
      (node (ref "X7") (pin "3") (pinfunction "KL_3") (pintype "passive"))
    )
    (net (code "50") (name "Net-(U$3-OUT2B)") (class "Default")
      (node (ref "U$3") (pin "P22") (pinfunction "OUT2B_P22") (pintype "bidirectional"))
      (node (ref "X7") (pin "4") (pinfunction "KL_4") (pintype "passive"))
    )
    (net (code "51") (name "Net-(U$3-ROSC)") (class "Default")
      (node (ref "R18") (pin "2") (pinfunction "2_2") (pintype "passive"))
      (node (ref "U$3") (pin "P8") (pinfunction "ROSC_P8") (pintype "bidirectional"))
    )
    (net (code "52") (name "Net-(U$3-SENSE1)") (class "Default")
      (node (ref "R20") (pin "1") (pinfunction "1_1") (pintype "passive"))
      (node (ref "U$3") (pin "P17") (pinfunction "SENSE1_P17") (pintype "bidirectional"))
    )
    (net (code "53") (name "Net-(U$3-SENSE2)") (class "Default")
      (node (ref "R19") (pin "1") (pinfunction "1_1") (pintype "passive"))
      (node (ref "U$3") (pin "P20") (pinfunction "SENSE2_P20") (pintype "bidirectional"))
    )
    (net (code "54") (name "Net-(U$3-VCP)") (class "Default")
      (node (ref "C54") (pin "1") (pinfunction "1_1") (pintype "passive"))
      (node (ref "U$3") (pin "P3") (pinfunction "VCP_P3") (pintype "bidirectional"))
    )
    (net (code "55") (name "Net-(U$3-VREG)") (class "Default")
      (node (ref "C38") (pin "2") (pinfunction "2_2") (pintype "passive"))
      (node (ref "U$3") (pin "P4") (pinfunction "VREG_P4") (pintype "bidirectional"))
    )
    (net (code "56") (name "Net-(U$3-~{RESET})") (class "Default")
      (node (ref "R17") (pin "2") (pinfunction "2_2") (pintype "passive"))
      (node (ref "U$3") (pin "P7") (pinfunction "~{RESET}_P7") (pintype "bidirectional"))
    )
    (net (code "57") (name "Net-(U$3-~{SLEEP})") (class "Default")
      (node (ref "R30") (pin "2") (pinfunction "2_2") (pintype "passive"))
      (node (ref "U$3") (pin "P9") (pinfunction "~{SLEEP}_P9") (pintype "bidirectional"))
    )
    (net (code "58") (name "Net-(U$4-1)") (class "Default")
      (node (ref "R28") (pin "1") (pinfunction "1_1") (pintype "passive"))
      (node (ref "U$4") (pin "P1") (pinfunction "1_P1") (pintype "bidirectional"))
    )
    (net (code "59") (name "Net-(U$4-3)") (class "Default")
      (node (ref "JP2") (pin "2") (pinfunction "2_2") (pintype "passive"))
      (node (ref "U$4") (pin "P3") (pinfunction "3_P3") (pintype "bidirectional"))
    )
    (net (code "60") (name "Net-(U$4-4)") (class "Default")
      (node (ref "JP2") (pin "1") (pinfunction "1_1") (pintype "passive"))
      (node (ref "U$4") (pin "P4") (pinfunction "4_P4") (pintype "bidirectional"))
    )
    (net (code "61") (name "Net-(U1-AREF)") (class "Default")
      (node (ref "C6") (pin "1") (pinfunction "1_1") (pintype "passive"))
      (node (ref "U1") (pin "42") (pinfunction "AREF_42") (pintype "input"))
    )
    (net (code "62") (name "Net-(U1-UCAP)") (class "Default")
      (node (ref "C7") (pin "1") (pinfunction "1_1") (pintype "passive"))
      (node (ref "U1") (pin "6") (pinfunction "UCAP_6") (pintype "power_in"))
    )
    (net (code "63") (name "Net-(U2-BST)") (class "Default")
      (node (ref "C48") (pin "1") (pinfunction "1_1") (pintype "passive"))
      (node (ref "U2") (pin "1") (pinfunction "BST_1") (pintype "power_in"))
    )
    (net (code "64") (name "Net-(U2-EN)") (class "Default")
      (node (ref "C47") (pin "1") (pinfunction "1_1") (pintype "passive"))
      (node (ref "R29") (pin "2") (pinfunction "2_2") (pintype "passive"))
      (node (ref "U$7") (pin "P$2") (pinfunction "P$2_P$2") (pintype "bidirectional"))
      (node (ref "U2") (pin "2") (pinfunction "VIN_2") (pintype "power_in"))
      (node (ref "U2") (pin "3") (pinfunction "EN_3") (pintype "input"))
    )
    (net (code "65") (name "Net-(U2-PGOOD)") (class "Default")
      (node (ref "R29") (pin "1") (pinfunction "1_1") (pintype "passive"))
      (node (ref "U2") (pin "4") (pinfunction "PGOOD_4") (pintype "output"))
    )
    (net (code "66") (name "Net-(U2-SW)") (class "Default")
      (node (ref "C48") (pin "2") (pinfunction "2_2") (pintype "passive"))
      (node (ref "U$5") (pin "P$2") (pinfunction "P$2_P$2") (pintype "bidirectional"))
      (node (ref "U$6") (pin "P$2") (pinfunction "P$2_P$2") (pintype "bidirectional"))
      (node (ref "U2") (pin "8") (pinfunction "SW_8") (pintype "output"))
    )
    (net (code "67") (name "SHUTTER") (class "Default")
      (node (ref "R28") (pin "2") (pinfunction "2_2") (pintype "passive"))
      (node (ref "U1") (pin "1") (pinfunction "PE6(INT6/AIN0)_1") (pintype "bidirectional"))
    )
    (net (code "68") (name "START{slash}STOP") (class "Default")
      (node (ref "SW9") (pin "A") (pinfunction "P_A") (pintype "passive"))
      (node (ref "U1") (pin "10") (pinfunction "PB2(PDI/PCINT2/MOSI)_10") (pintype "bidirectional"))
    )
    (net (code "69") (name "STEP1") (class "Default")
      (node (ref "U$1") (pin "P11") (pinfunction "STEP_P11") (pintype "bidirectional"))
      (node (ref "U1") (pin "30") (pinfunction "PB6(PCINT6/OC1B/OC4B/ADC13)_30") (pintype "bidirectional"))
    )
    (net (code "70") (name "STEP2") (class "Default")
      (node (ref "U$2") (pin "P11") (pinfunction "STEP_P11") (pintype "bidirectional"))
      (node (ref "U1") (pin "29") (pinfunction "PB5(PCINT5/OC1A/~{OC4B/ADC12})_29") (pintype "bidirectional"))
    )
    (net (code "71") (name "STEP3") (class "Default")
      (node (ref "U$3") (pin "P11") (pinfunction "STEP_P11") (pintype "bidirectional"))
      (node (ref "U1") (pin "31") (pinfunction "PC6(OC3A/~{OC4A})_31") (pintype "bidirectional"))
    )
    (net (code "72") (name "STOP1") (class "Default")
      (node (ref "C28") (pin "1") (pinfunction "1_1") (pintype "passive"))
      (node (ref "R25") (pin "1") (pinfunction "1_1") (pintype "passive"))
      (node (ref "U1") (pin "37") (pinfunction "PF6(ADO6/TDO)_37") (pintype "bidirectional"))
      (node (ref "X3") (pin "2") (pinfunction "S_2") (pintype "passive"))
    )
    (net (code "73") (name "STOP2") (class "Default")
      (node (ref "C27") (pin "1") (pinfunction "1_1") (pintype "passive"))
      (node (ref "R26") (pin "1") (pinfunction "1_1") (pintype "passive"))
      (node (ref "U1") (pin "36") (pinfunction "PF7(ADC7/TDI)_36") (pintype "bidirectional"))
      (node (ref "X3") (pin "4") (pinfunction "S_4") (pintype "passive"))
    )
    (net (code "74") (name "STOP3") (class "Default")
      (node (ref "C26") (pin "1") (pinfunction "1_1") (pintype "passive"))
      (node (ref "R12") (pin "1") (pinfunction "1_1") (pintype "passive"))
      (node (ref "U1") (pin "39") (pinfunction "PF4(ADC4/TCK)_39") (pintype "bidirectional"))
      (node (ref "X2") (pin "2") (pinfunction "S_2") (pintype "passive"))
    )
    (net (code "75") (name "STOP4") (class "Default")
      (node (ref "C25") (pin "1") (pinfunction "1_1") (pintype "passive"))
      (node (ref "R24") (pin "1") (pinfunction "1_1") (pintype "passive"))
      (node (ref "U1") (pin "38") (pinfunction "PF5(ADC5/TMS)_38") (pintype "bidirectional"))
      (node (ref "X2") (pin "4") (pinfunction "S_4") (pintype "passive"))
    )
    (net (code "76") (name "STOP5") (class "Default")
      (node (ref "C23") (pin "1") (pinfunction "1_1") (pintype "passive"))
      (node (ref "R6") (pin "1") (pinfunction "1_1") (pintype "passive"))
      (node (ref "U1") (pin "41") (pinfunction "PF0(ADO0)_41") (pintype "bidirectional"))
      (node (ref "X1") (pin "2") (pinfunction "S_2") (pintype "passive"))
    )
    (net (code "77") (name "STOP6") (class "Default")
      (node (ref "C22") (pin "1") (pinfunction "1_1") (pintype "passive"))
      (node (ref "R7") (pin "1") (pinfunction "1_1") (pintype "passive"))
      (node (ref "U1") (pin "40") (pinfunction "PF1(ADC1)_40") (pintype "bidirectional"))
      (node (ref "X1") (pin "4") (pinfunction "S_4") (pintype "passive"))
    )
    (net (code "78") (name "T0{slash}OC4D") (class "Default")
      (node (ref "R27") (pin "2") (pinfunction "2_2") (pintype "passive"))
      (node (ref "U1") (pin "27") (pinfunction "PD7(T0/OC4D/ADC10)_27") (pintype "bidirectional"))
    )
    (net (code "79") (name "UART_RX") (class "Default")
      (node (ref "R21") (pin "2") (pinfunction "2_2") (pintype "passive"))
      (node (ref "U1") (pin "20") (pinfunction "PD2(RXD/INT2)_20") (pintype "bidirectional"))
    )
    (net (code "80") (name "UART_TX") (class "Default")
      (node (ref "R22") (pin "2") (pinfunction "2_2") (pintype "passive"))
      (node (ref "U1") (pin "21") (pinfunction "PD3(TXD1/INT3)_21") (pintype "bidirectional"))
    )
    (net (code "81") (name "USB_D+") (class "Default")
      (node (ref "R4") (pin "2") (pinfunction "2_2") (pintype "passive"))
      (node (ref "U1") (pin "4") (pinfunction "D+_4") (pintype "passive"))
    )
    (net (code "82") (name "USB_D-") (class "Default")
      (node (ref "R3") (pin "2") (pinfunction "2_2") (pintype "passive"))
      (node (ref "U1") (pin "3") (pinfunction "D-_3") (pintype "passive"))
    )
    (net (code "83") (name "VCC") (class "Default")
      (node (ref "C1") (pin "1") (pinfunction "1_1") (pintype "passive"))
      (node (ref "C13") (pin "2") (pinfunction "2_2") (pintype "passive"))
      (node (ref "C2") (pin "1") (pinfunction "1_1") (pintype "passive"))
      (node (ref "C3") (pin "1") (pinfunction "1_1") (pintype "passive"))
      (node (ref "C31") (pin "2") (pinfunction "2_2") (pintype "passive"))
      (node (ref "C4") (pin "1") (pinfunction "1_1") (pintype "passive"))
      (node (ref "C40") (pin "2") (pinfunction "2_2") (pintype "passive"))
      (node (ref "C49") (pin "2") (pinfunction "2_2") (pintype "passive"))
      (node (ref "C5") (pin "1") (pinfunction "1_1") (pintype "passive"))
      (node (ref "C50") (pin "2") (pinfunction "2_2") (pintype "passive"))
      (node (ref "C51") (pin "1") (pinfunction "1_1") (pintype "passive"))
      (node (ref "C52") (pin "2") (pinfunction "2_2") (pintype "passive"))
      (node (ref "C53") (pin "2") (pinfunction "2_2") (pintype "passive"))
      (node (ref "C54") (pin "2") (pinfunction "2_2") (pintype "passive"))
      (node (ref "F1") (pin "P$2") (pinfunction "P$2_P$2") (pintype "bidirectional"))
      (node (ref "JP1") (pin "4") (pinfunction "4_4") (pintype "passive"))
      (node (ref "R1") (pin "2") (pinfunction "2_2") (pintype "passive"))
      (node (ref "R12") (pin "2") (pinfunction "2_2") (pintype "passive"))
      (node (ref "R13") (pin "1") (pinfunction "1_1") (pintype "passive"))
      (node (ref "R17") (pin "1") (pinfunction "1_1") (pintype "passive"))
      (node (ref "R2") (pin "1") (pinfunction "1_1") (pintype "passive"))
      (node (ref "R24") (pin "2") (pinfunction "2_2") (pintype "passive"))
      (node (ref "R25") (pin "2") (pinfunction "2_2") (pintype "passive"))
      (node (ref "R26") (pin "2") (pinfunction "2_2") (pintype "passive"))
      (node (ref "R30") (pin "1") (pinfunction "1_1") (pintype "passive"))
      (node (ref "R31") (pin "1") (pinfunction "1_1") (pintype "passive"))
      (node (ref "R32") (pin "1") (pinfunction "1_1") (pintype "passive"))
      (node (ref "R5") (pin "2") (pinfunction "2_2") (pintype "passive"))
      (node (ref "R6") (pin "2") (pinfunction "2_2") (pintype "passive"))
      (node (ref "R7") (pin "2") (pinfunction "2_2") (pintype "passive"))
      (node (ref "R8") (pin "1") (pinfunction "1_1") (pintype "passive"))
      (node (ref "U$1") (pin "P10") (pinfunction "VDD_P10") (pintype "bidirectional"))
      (node (ref "U$2") (pin "P10") (pinfunction "VDD_P10") (pintype "bidirectional"))
      (node (ref "U$3") (pin "P10") (pinfunction "VDD_P10") (pintype "bidirectional"))
      (node (ref "U$6") (pin "P$1") (pinfunction "P$1_P$1") (pintype "bidirectional"))
      (node (ref "U1") (pin "14") (pinfunction "VCC_2_14") (pintype "power_in"))
      (node (ref "U1") (pin "2") (pinfunction "UVCC_2") (pintype "power_in"))
      (node (ref "U1") (pin "24") (pinfunction "AVCC_2_24") (pintype "power_in"))
      (node (ref "U1") (pin "34") (pinfunction "VCC_34") (pintype "power_in"))
      (node (ref "U1") (pin "44") (pinfunction "AVCC_44") (pintype "power_in"))
      (node (ref "U1") (pin "7") (pinfunction "VBUS_7") (pintype "input"))
      (node (ref "U2") (pin "5") (pinfunction "FB_5") (pintype "input"))
    )
    (net (code "84") (name "VREF") (class "Default")
      (node (ref "C12") (pin "2") (pinfunction "2_2") (pintype "passive"))
      (node (ref "R27") (pin "1") (pinfunction "1_1") (pintype "passive"))
      (node (ref "U$1") (pin "P12") (pinfunction "REF_P12") (pintype "bidirectional"))
      (node (ref "U$2") (pin "P12") (pinfunction "REF_P12") (pintype "bidirectional"))
      (node (ref "U$3") (pin "P12") (pinfunction "REF_P12") (pintype "bidirectional"))
    )
    (net (code "85") (name "XTAL1") (class "Default")
      (node (ref "C8") (pin "1") (pinfunction "1_1") (pintype "passive"))
      (node (ref "Q2") (pin "1") (pinfunction "1_1") (pintype "passive"))
      (node (ref "U1") (pin "17") (pinfunction "XTAL1_17") (pintype "input"))
    )
    (net (code "86") (name "XTAL2") (class "Default")
      (node (ref "C9") (pin "1") (pinfunction "1_1") (pintype "passive"))
      (node (ref "Q2") (pin "2") (pinfunction "2_2") (pintype "passive"))
      (node (ref "U1") (pin "16") (pinfunction "XTAL2_16") (pintype "output"))
    )
    (net (code "87") (name "unconnected-(CN1-PadID)") (class "Default")
      (node (ref "CN1") (pin "ID") (pinfunction "ID_ID") (pintype "bidirectional"))
    )
    (net (code "88") (name "unconnected-(SW7-P1-PadA')") (class "Default")
      (node (ref "SW7") (pin "A'") (pinfunction "P1_A'") (pintype "passive"))
    )
    (net (code "89") (name "unconnected-(SW7-S1-PadB')") (class "Default")
      (node (ref "SW7") (pin "B'") (pinfunction "S1_B'") (pintype "passive"))
    )
    (net (code "90") (name "unconnected-(SW8-P1-PadA')") (class "Default")
      (node (ref "SW8") (pin "A'") (pinfunction "P1_A'") (pintype "passive"))
    )
    (net (code "91") (name "unconnected-(SW8-S1-PadB')") (class "Default")
      (node (ref "SW8") (pin "B'") (pinfunction "S1_B'") (pintype "passive"))
    )
    (net (code "92") (name "unconnected-(SW9-P1-PadA')") (class "Default")
      (node (ref "SW9") (pin "A'") (pinfunction "P1_A'") (pintype "passive"))
    )
    (net (code "93") (name "unconnected-(SW9-S1-PadB')") (class "Default")
      (node (ref "SW9") (pin "B'") (pinfunction "S1_B'") (pintype "passive"))
    )
    (net (code "94") (name "unconnected-(U1-PB3(PDO{slash}PCINT3{slash}MISO)-Pad11)") (class "Default")
      (node (ref "U1") (pin "11") (pinfunction "PB3(PDO/PCINT3/MISO)_11") (pintype "bidirectional"))
    )
    (net (code "95") (name "unconnected-(U1-PB7(PCINT7{slash}OC0A{slash}OC1C{slash}~{RTS})-Pad12)") (class "Default")
      (node (ref "U1") (pin "12") (pinfunction "PB7(PCINT7/OC0A/OC1C/~{RTS})_12") (pintype "bidirectional"))
    )
    (net (code "96") (name "unconnected-(U1-PD0(OC0B{slash}SCL{slash}INT0)-Pad18)") (class "Default")
      (node (ref "U1") (pin "18") (pinfunction "PD0(OC0B/SCL/INT0)_18") (pintype "bidirectional"))
    )
    (net (code "97") (name "unconnected-(U1-PD4(ICP1{slash}ADC8)-Pad25)") (class "Default")
      (node (ref "U1") (pin "25") (pinfunction "PD4(ICP1/ADC8)_25") (pintype "bidirectional"))
    )
    (net (code "98") (name "unconnected-(U1-PD6(T1{slash}~{OC4D{slash}ADC9})-Pad26)") (class "Default")
      (node (ref "U1") (pin "26") (pinfunction "PD6(T1/~{OC4D/ADC9})_26") (pintype "bidirectional"))
    )
    (net (code "99") (name "unconnected-(U2-NC-Pad6)") (class "Default")
      (node (ref "U2") (pin "6") (pinfunction "NC_6") (pintype "no_connect"))
    )
  )
)
